# E-17_MIPI_DSI_MIPI_CSI.net
KiCad netlist of a schematic drawn in Altium Designer
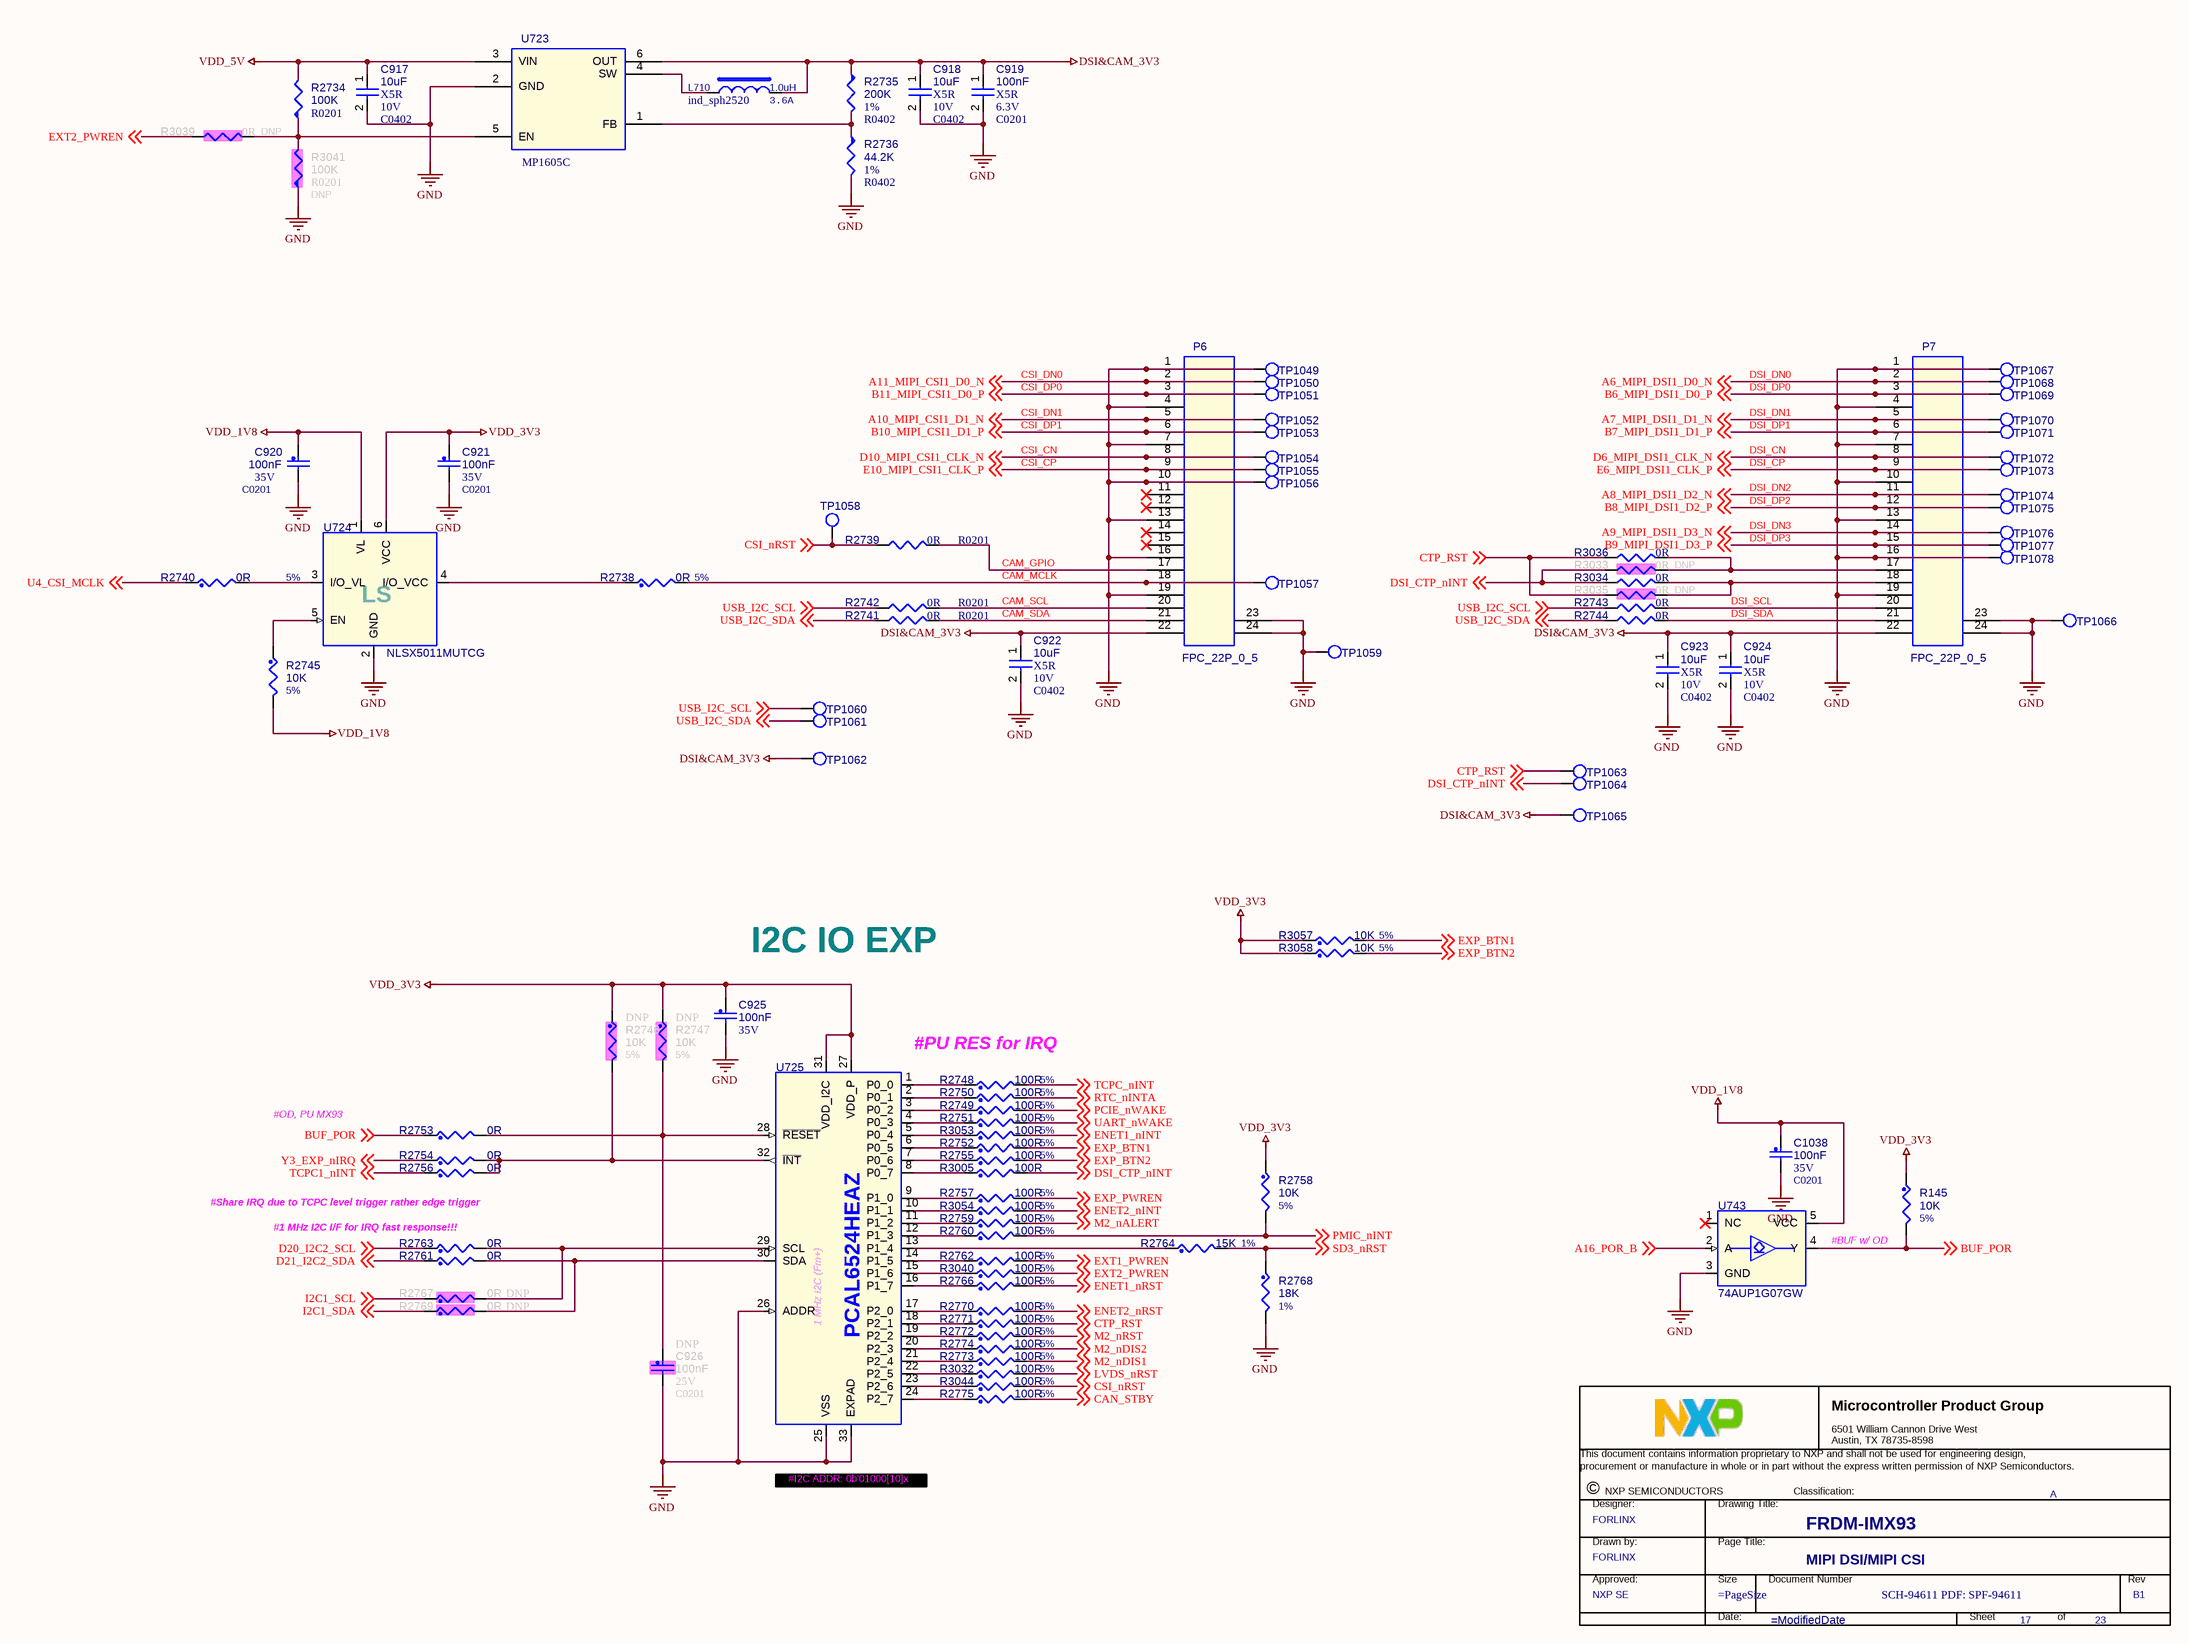
[diagram p0: E-17 MIPI DSI_MIPI CSI.SchDoc]

(export (version "E")
  (design (tool "Eeschema 10.0.6"))
  (components
    (comp (ref "C917")
      (value "10uF")
      (footprint "C0402")
      (description "0402,10uF,6.3V,+/-20%,X5R")
      (fields
        (field (name "VOLTAGE") "10V")
        (field (name "PCB FOOTPRINT") "C0402")
        (field (name "DIELECTRIC") "X5R")
        (field (name "TOLERANCE") "±20%")
        (field (name "MANUFACTURER") "murata")
        (field (name "CREATED BY") "JJJ")
      )
      (libsource (lib "*") (part "CAP NP"))
    )
    (comp (ref "C918")
      (value "10uF")
      (footprint "C0402")
      (description "0402,10uF,6.3V,+/-20%,X5R")
      (fields
        (field (name "VOLTAGE") "10V")
        (field (name "PCB FOOTPRINT") "C0402")
        (field (name "DIELECTRIC") "X5R")
        (field (name "MANUFACTURER") "TDK")
        (field (name "TOLERANCE") "10%")
        (field (name "CREATED BY") "JJJ")
      )
      (libsource (lib "*") (part "CAP NP"))
    )
    (comp (ref "C919")
      (value "100nF")
      (footprint "C0201")
      (description "0201,100nF,25V,+/-10%,X5R")
      (fields
        (field (name "VOLTAGE") "6.3V")
        (field (name "PCB FOOTPRINT") "C0201")
        (field (name "DIELECTRIC") "X5R")
        (field (name "MANUFACTURER") "FH(风华)")
        (field (name "TOLERANCE") "±10%")
        (field (name "CREATED BY") "JJJ")
      )
      (libsource (lib "*") (part "CAP NP"))
    )
    (comp (ref "C920")
      (value "100nF")
      (footprint "C0201")
      (description "0201,100nF,25V,+/-10%,X5R")
      (fields
        (field (name "PCB FOOTPRINT") "C0201")
        (field (name "VOLTAGE") "35V")
        (field (name "TOLERANCE") "10%")
      )
      (libsource (lib "*") (part "CAP_NP"))
    )
    (comp (ref "C921")
      (value "100nF")
      (footprint "C0201")
      (description "0201,100nF,25V,+/-10%,X5R")
      (fields
        (field (name "PCB FOOTPRINT") "C0201")
        (field (name "TOLERANCE") "10%")
        (field (name "VOLTAGE") "35V")
      )
      (libsource (lib "*") (part "CAP_NP"))
    )
    (comp (ref "C922")
      (value "10uF")
      (footprint "C0402")
      (description "0402,10uF,6.3V,+/-20%,X5R")
      (fields
        (field (name "VOLTAGE") "10V")
        (field (name "PCB FOOTPRINT") "C0402")
        (field (name "DIELECTRIC") "X5R")
        (field (name "MANUFACTURER") "TDK")
        (field (name "TOLERANCE") "10%")
        (field (name "CREATED BY") "JJJ")
      )
      (libsource (lib "*") (part "CAP NP"))
    )
    (comp (ref "C923")
      (value "10uF")
      (footprint "C0402")
      (description "0402,10uF,6.3V,+/-20%,X5R")
      (fields
        (field (name "VOLTAGE") "10V")
        (field (name "PCB FOOTPRINT") "C0402")
        (field (name "DIELECTRIC") "X5R")
        (field (name "MANUFACTURER") "TDK")
        (field (name "TOLERANCE") "10%")
        (field (name "CREATED BY") "JJJ")
      )
      (libsource (lib "*") (part "CAP NP"))
    )
    (comp (ref "C924")
      (value "10uF")
      (footprint "C0402")
      (description "0402,10uF,6.3V,+/-20%,X5R")
      (fields
        (field (name "VOLTAGE") "10V")
        (field (name "PCB FOOTPRINT") "C0402")
        (field (name "DIELECTRIC") "X5R")
        (field (name "TOLERANCE") "10%")
        (field (name "MANUFACTURER") "TDK")
        (field (name "CREATED BY") "JJJ")
      )
      (libsource (lib "*") (part "CAP NP"))
    )
    (comp (ref "C925")
      (value "100nF")
      (footprint "C0402")
      (description "0402,100nF,50V,+/-10%,X5R")
      (fields (field (name "TOLERANCE") "10%") (field (name "VOLTAGE") "35V"))
      (libsource (lib "*") (part "CAP_NP"))
    )
    (comp (ref "C926")
      (value "100nF")
      (footprint "C0201")
      (description "0201,100nF,25V,+/-10%,X5R")
      (fields
        (field (name "ASSY_OPT") "DNP")
        (field (name "PCB FOOTPRINT") "C0201")
        (field (name "TOLERANCE") "10%")
        (field (name "VOLTAGE") "25V")
      )
      (libsource (lib "*") (part "CAP_NP"))
    )
    (comp (ref "C1038")
      (value "100nF")
      (footprint "C0201")
      (description "0201,100nF,25V,+/-10%,X5R")
      (fields
        (field (name "PCB FOOTPRINT") "C0201")
        (field (name "TOLERANCE") "10%")
        (field (name "VOLTAGE") "35V")
      )
      (libsource (lib "*") (part "CAP_NP"))
    )
    (comp (ref "L710")
      (value "1.0uH")
      (footprint "ind_sph2520")
      (description "1uH ,2.5*2.0*1.2mm, 3.6A")
      (fields
        (field (name "ISAT") "3.6A")
        (field (name "PCB FOOTPRINT") "ind_sph2520")
        (field (name "MANUFACTURER") "TDK")
        (field (name "TOLERANCE") "20%")
        (field (name "CREATED BY") "JJJ")
      )
      (libsource (lib "*") (part "INDUCTORS OF FERRITE"))
    )
    (comp (ref "P6")
      (value "FPC_22P_0_5")
      (footprint "fpc_22p_0_5")
      (description "22P,0.5mm,A")
      (libsource (lib "*") (part "FPC_22P_0_5"))
    )
    (comp (ref "P7")
      (value "FPC_22P_0_5")
      (footprint "fpc_22p_0_5")
      (description "22P,0.5mm,A")
      (libsource (lib "*") (part "FPC_22P_0_5"))
    )
    (comp (ref "R145")
      (value "10K")
      (footprint "R0201")
      (description "0201,10K,+/-5%")
      (fields (field (name "TOLERANCE") "5%"))
      (libsource (lib "*") (part "RES"))
    )
    (comp (ref "R2734")
      (value "100K")
      (footprint "R0201")
      (description "0201,100K,+/-1%")
      (fields
        (field (name "TOLERANCE") "5%")
        (field (name "PCB FOOTPRINT") "R0201")
        (field (name "MANUFACTURER") "YAGEO")
        (field (name "CREATED BY") "YTL")
      )
      (libsource (lib "*") (part "RESISTOR5"))
    )
    (comp (ref "R2735")
      (value "200K")
      (footprint "R0402")
      (description "0402,200K,+/-1%")
      (fields
        (field (name "PCB FOOTPRINT") "R0402")
        (field (name "TOLERANCE") "1%")
        (field (name "MANUFACTURER") "YAGEO")
        (field (name "CREATED BY") "YTL")
      )
      (libsource (lib "*") (part "RESISTOR1"))
    )
    (comp (ref "R2736")
      (value "44.2K")
      (footprint "R0402")
      (description "0402,44.2K,+/-1%")
      (fields
        (field (name "PCB FOOTPRINT") "R0402")
        (field (name "TOLERANCE") "1%")
        (field (name "MANUFACTURER") "YAGEO")
        (field (name "CREATED BY") "YTL")
      )
      (libsource (lib "*") (part "RESISTOR1"))
    )
    (comp (ref "R2738")
      (value "0R")
      (footprint "R0201")
      (description "0201,0Ohm,+/-5%")
      (fields (field (name "VOLTAGE") "1/16W") (field (name "TOLERANCE") "5%"))
      (libsource (lib "*") (part "RES"))
    )
    (comp (ref "R2739")
      (value "0R")
      (footprint "R0201")
      (description "0201,0Ohm,+/-5%")
      (fields (field (name "PCB FOOTPRINT") "R0201"))
      (libsource (lib "*") (part "R0402,4.7K_Dup1"))
    )
    (comp (ref "R2740")
      (value "0R")
      (footprint "R0201")
      (description "0201,0Ohm,+/-5%")
      (fields (field (name "VOLTAGE") "1/16W") (field (name "TOLERANCE") "5%"))
      (libsource (lib "*") (part "RES"))
    )
    (comp (ref "R2741")
      (value "0R")
      (footprint "R0201")
      (description "0201,0Ohm,+/-5%")
      (fields (field (name "PCB FOOTPRINT") "R0201"))
      (libsource (lib "*") (part "R0402,4.7K_Dup1"))
    )
    (comp (ref "R2742")
      (value "0R")
      (footprint "R0201")
      (description "0201,0Ohm,+/-5%")
      (fields (field (name "PCB FOOTPRINT") "R0201"))
      (libsource (lib "*") (part "R0402,4.7K_Dup1"))
    )
    (comp (ref "R2743")
      (value "0R")
      (footprint "R0201")
      (description "0201,0Ohm,+/-5%")
      (libsource (lib "*") (part "R0402,4.7K_Dup1"))
    )
    (comp (ref "R2744")
      (value "0R")
      (footprint "R0201")
      (description "0201,0Ohm,+/-5%")
      (libsource (lib "*") (part "R0402,4.7K_Dup1"))
    )
    (comp (ref "R2745")
      (value "10K")
      (footprint "R0201")
      (description "0201,10K,+/-5%")
      (fields (field (name "TOLERANCE") "5%"))
      (libsource (lib "*") (part "RES"))
    )
    (comp (ref "R2746")
      (value "10K")
      (footprint "R0201")
      (description "0201,10K,+/-5%")
      (fields (field (name "ASSY_OPT") "DNP") (field (name "TOLERANCE") "5%"))
      (libsource (lib "*") (part "RES"))
    )
    (comp (ref "R2747")
      (value "10K")
      (footprint "R0201")
      (description "0201,10K,+/-5%")
      (fields (field (name "ASSY_OPT") "DNP") (field (name "TOLERANCE") "5%"))
      (libsource (lib "*") (part "RES"))
    )
    (comp (ref "R2748")
      (value "100R")
      (footprint "R0201")
      (description "0201,100Ohm,+/-1%")
      (fields (field (name "TOLERANCE") "5%"))
      (libsource (lib "*") (part "RES"))
    )
    (comp (ref "R2749")
      (value "100R")
      (footprint "R0201")
      (description "0201,100Ohm,+/-1%")
      (fields (field (name "TOLERANCE") "5%"))
      (libsource (lib "*") (part "RES"))
    )
    (comp (ref "R2750")
      (value "100R")
      (footprint "R0201")
      (description "0201,100Ohm,+/-1%")
      (fields (field (name "TOLERANCE") "5%"))
      (libsource (lib "*") (part "RES"))
    )
    (comp (ref "R2751")
      (value "100R")
      (footprint "R0201")
      (description "0201,100Ohm,+/-1%")
      (fields (field (name "TOLERANCE") "5%"))
      (libsource (lib "*") (part "RES"))
    )
    (comp (ref "R2752")
      (value "100R")
      (footprint "R0201")
      (description "0201,100Ohm,+/-1%")
      (fields (field (name "TOLERANCE") "5%"))
      (libsource (lib "*") (part "RES"))
    )
    (comp (ref "R2753")
      (value "0R")
      (footprint "R0201")
      (description "0201,0Ohm,+/-5%")
      (fields (field (name "VOLTAGE") "1/16W") (field (name "TOLERANCE") "5%"))
      (libsource (lib "*") (part "RES"))
    )
    (comp (ref "R2754")
      (value "0R")
      (footprint "R0201")
      (description "0201,0Ohm,+/-5%")
      (fields (field (name "TOLERANCE") "5%") (field (name "VOLTAGE") "1/16W"))
      (libsource (lib "*") (part "RES"))
    )
    (comp (ref "R2755")
      (value "100R")
      (footprint "R0201")
      (description "0201,100Ohm,+/-1%")
      (fields (field (name "TOLERANCE") "5%"))
      (libsource (lib "*") (part "RES"))
    )
    (comp (ref "R2756")
      (value "0R")
      (footprint "R0201")
      (description "0201,0Ohm,+/-5%")
      (fields (field (name "VOLTAGE") "1/16W") (field (name "TOLERANCE") "5%"))
      (libsource (lib "*") (part "RES"))
    )
    (comp (ref "R2757")
      (value "100R")
      (footprint "R0201")
      (description "0201,100Ohm,+/-1%")
      (fields (field (name "TOLERANCE") "5%"))
      (libsource (lib "*") (part "RES"))
    )
    (comp (ref "R2758")
      (value "10K")
      (footprint "R0201")
      (description "0201,10K,+/-5%")
      (fields (field (name "TOLERANCE") "5%"))
      (libsource (lib "*") (part "RES"))
    )
    (comp (ref "R2759")
      (value "100R")
      (footprint "R0201")
      (description "0201,100Ohm,+/-1%")
      (fields (field (name "TOLERANCE") "5%"))
      (libsource (lib "*") (part "RES"))
    )
    (comp (ref "R2760")
      (value "100R")
      (footprint "R0201")
      (description "0201,100Ohm,+/-1%")
      (fields (field (name "TOLERANCE") "5%"))
      (libsource (lib "*") (part "RES"))
    )
    (comp (ref "R2761")
      (value "0R")
      (footprint "R0201")
      (description "0201,0Ohm,+/-5%")
      (fields (field (name "TOLERANCE") "5%") (field (name "VOLTAGE") "1/16W"))
      (libsource (lib "*") (part "RES"))
    )
    (comp (ref "R2762")
      (value "100R")
      (footprint "R0201")
      (description "0201,100Ohm,+/-1%")
      (fields (field (name "TOLERANCE") "5%"))
      (libsource (lib "*") (part "RES"))
    )
    (comp (ref "R2763")
      (value "0R")
      (footprint "R0201")
      (description "0201,0Ohm,+/-5%")
      (fields (field (name "TOLERANCE") "5%") (field (name "VOLTAGE") "1/16W"))
      (libsource (lib "*") (part "RES"))
    )
    (comp (ref "R2764")
      (value "15K")
      (footprint "R0402")
      (description "0402,15K,+/-1%")
      (fields (field (name "TOLERANCE") "1%"))
      (libsource (lib "*") (part "RES"))
    )
    (comp (ref "R2766")
      (value "100R")
      (footprint "R0201")
      (description "0201,100Ohm,+/-1%")
      (fields (field (name "TOLERANCE") "5%"))
      (libsource (lib "*") (part "RES"))
    )
    (comp (ref "R2767")
      (value "0R")
      (footprint "R0201")
      (description "0201,0Ohm,+/-5%")
      (fields
        (field (name "ASSY_OPT") "DNP")
        (field (name "TOLERANCE") "5%")
        (field (name "VOLTAGE") "1/16W")
      )
      (libsource (lib "*") (part "RES"))
    )
    (comp (ref "R2768")
      (value "18K")
      (footprint "R0402")
      (description "0402,18K,+/-1%")
      (fields (field (name "VOLTAGE") "50V") (field (name "TOLERANCE") "1%"))
      (libsource (lib "*") (part "RES"))
    )
    (comp (ref "R2769")
      (value "0R")
      (footprint "R0201")
      (description "0201,0Ohm,+/-5%")
      (fields
        (field (name "ASSY_OPT") "DNP")
        (field (name "VOLTAGE") "1/16W")
        (field (name "TOLERANCE") "5%")
      )
      (libsource (lib "*") (part "RES"))
    )
    (comp (ref "R2770")
      (value "100R")
      (footprint "R0201")
      (description "0201,100Ohm,+/-1%")
      (fields (field (name "TOLERANCE") "5%"))
      (libsource (lib "*") (part "RES"))
    )
    (comp (ref "R2771")
      (value "100R")
      (footprint "R0201")
      (description "0201,100Ohm,+/-1%")
      (fields (field (name "TOLERANCE") "5%"))
      (libsource (lib "*") (part "RES"))
    )
    (comp (ref "R2772")
      (value "100R")
      (footprint "R0201")
      (description "0201,100Ohm,+/-1%")
      (fields (field (name "TOLERANCE") "5%"))
      (libsource (lib "*") (part "RES"))
    )
    (comp (ref "R2773")
      (value "100R")
      (footprint "R0201")
      (description "0201,100Ohm,+/-1%")
      (fields (field (name "TOLERANCE") "5%"))
      (libsource (lib "*") (part "RES"))
    )
    (comp (ref "R2774")
      (value "100R")
      (footprint "R0201")
      (description "0201,100Ohm,+/-1%")
      (fields (field (name "TOLERANCE") "5%"))
      (libsource (lib "*") (part "RES"))
    )
    (comp (ref "R2775")
      (value "100R")
      (footprint "R0201")
      (description "0201,100Ohm,+/-1%")
      (fields (field (name "TOLERANCE") "5%"))
      (libsource (lib "*") (part "RES"))
    )
    (comp (ref "R3005")
      (value "100R")
      (footprint "R0201")
      (description "0201,100Ohm,+/-1%")
      (fields (field (name "TOLERANCE") "5%"))
      (libsource (lib "*") (part "RES"))
    )
    (comp (ref "R3032")
      (value "100R")
      (footprint "R0201")
      (description "0201,100Ohm,+/-1%")
      (fields (field (name "TOLERANCE") "5%"))
      (libsource (lib "*") (part "RES"))
    )
    (comp (ref "R3033")
      (value "0R")
      (footprint "R0201")
      (description "0201,0Ohm,+/-5%")
      (fields (field (name "ASSY_OPT") "DNP"))
      (libsource (lib "*") (part "R0402,4.7K_Dup1"))
    )
    (comp (ref "R3034")
      (value "0R")
      (footprint "R0201")
      (description "0201,0Ohm,+/-5%")
      (libsource (lib "*") (part "R0402,4.7K_Dup1"))
    )
    (comp (ref "R3035")
      (value "0R")
      (footprint "R0201")
      (description "0201,0Ohm,+/-5%")
      (fields (field (name "ASSY_OPT") "DNP"))
      (libsource (lib "*") (part "R0402,4.7K_Dup1"))
    )
    (comp (ref "R3036")
      (value "0R")
      (footprint "R0201")
      (description "0201,0Ohm,+/-5%")
      (libsource (lib "*") (part "R0402,4.7K_Dup1"))
    )
    (comp (ref "R3039")
      (value "0R")
      (footprint "R0201")
      (description "0201,0Ohm,+/-5%")
      (fields (field (name "ASSY_OPT") "DNP"))
      (libsource (lib "*") (part "R0402,4.7K_Dup1"))
    )
    (comp (ref "R3040")
      (value "100R")
      (footprint "R0201")
      (description "0201,100Ohm,+/-1%")
      (fields (field (name "TOLERANCE") "5%"))
      (libsource (lib "*") (part "RES"))
    )
    (comp (ref "R3041")
      (value "100K")
      (footprint "R0201")
      (description "0201,100K,+/-1%")
      (fields
        (field (name "TOLERANCE") "5%")
        (field (name "PCB FOOTPRINT") "R0201")
        (field (name "MANUFACTURER") "YAGEO")
        (field (name "ASSY_OPT") "DNP")
        (field (name "CREATED BY") "YTL")
      )
      (libsource (lib "*") (part "RESISTOR5"))
    )
    (comp (ref "R3044")
      (value "100R")
      (footprint "R0201")
      (description "0201,100Ohm,+/-1%")
      (fields (field (name "TOLERANCE") "5%"))
      (libsource (lib "*") (part "RES"))
    )
    (comp (ref "R3053")
      (value "100R")
      (footprint "R0201")
      (description "0201,100Ohm,+/-1%")
      (fields (field (name "TOLERANCE") "5%"))
      (libsource (lib "*") (part "RES"))
    )
    (comp (ref "R3054")
      (value "100R")
      (footprint "R0201")
      (description "0201,100Ohm,+/-1%")
      (fields (field (name "TOLERANCE") "5%"))
      (libsource (lib "*") (part "RES"))
    )
    (comp (ref "R3057")
      (value "10K")
      (footprint "R0201")
      (description "0201,10K,+/-5%")
      (fields (field (name "TOLERANCE") "5%"))
      (libsource (lib "*") (part "RES"))
    )
    (comp (ref "R3058")
      (value "10K")
      (footprint "R0201")
      (description "0201,10K,+/-5%")
      (fields (field (name "TOLERANCE") "5%"))
      (libsource (lib "*") (part "RES"))
    )
    (comp (ref "TP1049")
      (value "TPAD_020")
      (footprint "tpad_020")
      (description "no part to order")
      (libsource (lib "*") (part "T POINT R"))
    )
    (comp (ref "TP1050")
      (value "TPAD_020")
      (footprint "tpad_020")
      (description "no part to order")
      (libsource (lib "*") (part "T POINT R"))
    )
    (comp (ref "TP1051")
      (value "TPAD_020")
      (footprint "tpad_020")
      (description "no part to order")
      (libsource (lib "*") (part "T POINT R"))
    )
    (comp (ref "TP1052")
      (value "TPAD_020")
      (footprint "tpad_020")
      (description "no part to order")
      (libsource (lib "*") (part "T POINT R"))
    )
    (comp (ref "TP1053")
      (value "TPAD_020")
      (footprint "tpad_020")
      (description "no part to order")
      (libsource (lib "*") (part "T POINT R"))
    )
    (comp (ref "TP1054")
      (value "TPAD_020")
      (footprint "tpad_020")
      (description "no part to order")
      (libsource (lib "*") (part "T POINT R"))
    )
    (comp (ref "TP1055")
      (value "TPAD_020")
      (footprint "tpad_020")
      (description "no part to order")
      (libsource (lib "*") (part "T POINT R"))
    )
    (comp (ref "TP1056")
      (value "TPAD_020")
      (footprint "tpad_020")
      (description "no part to order")
      (libsource (lib "*") (part "T POINT R"))
    )
    (comp (ref "TP1057")
      (value "TPAD_020")
      (footprint "tpad_020")
      (description "no part to order")
      (libsource (lib "*") (part "T POINT R"))
    )
    (comp (ref "TP1058")
      (value "TPAD_020")
      (footprint "tpad_020")
      (description "no part to order")
      (libsource (lib "*") (part "T POINT R"))
    )
    (comp (ref "TP1059")
      (value "TPAD_020")
      (footprint "tpad_020")
      (description "no part to order")
      (libsource (lib "*") (part "T POINT R"))
    )
    (comp (ref "TP1060")
      (value "TPAD_020")
      (footprint "tpad_020")
      (description "no part to order")
      (libsource (lib "*") (part "T POINT R"))
    )
    (comp (ref "TP1061")
      (value "TPAD_020")
      (footprint "tpad_020")
      (description "no part to order")
      (libsource (lib "*") (part "T POINT R"))
    )
    (comp (ref "TP1062")
      (value "TPAD_020")
      (footprint "tpad_020")
      (description "no part to order")
      (libsource (lib "*") (part "T POINT R"))
    )
    (comp (ref "TP1063")
      (value "TPAD_020")
      (footprint "tpad_020")
      (description "no part to order")
      (libsource (lib "*") (part "T POINT R"))
    )
    (comp (ref "TP1064")
      (value "TPAD_020")
      (footprint "tpad_020")
      (description "no part to order")
      (libsource (lib "*") (part "T POINT R"))
    )
    (comp (ref "TP1065")
      (value "TPAD_020")
      (footprint "tpad_020")
      (description "no part to order")
      (libsource (lib "*") (part "T POINT R"))
    )
    (comp (ref "TP1066")
      (value "TPAD_020")
      (footprint "tpad_020")
      (description "no part to order")
      (libsource (lib "*") (part "T POINT R"))
    )
    (comp (ref "TP1067")
      (value "TPAD_020")
      (footprint "tpad_020")
      (description "no part to order")
      (libsource (lib "*") (part "T POINT R"))
    )
    (comp (ref "TP1068")
      (value "TPAD_020")
      (footprint "tpad_020")
      (description "no part to order")
      (libsource (lib "*") (part "T POINT R"))
    )
    (comp (ref "TP1069")
      (value "TPAD_020")
      (footprint "tpad_020")
      (description "no part to order")
      (libsource (lib "*") (part "T POINT R"))
    )
    (comp (ref "TP1070")
      (value "TPAD_020")
      (footprint "tpad_020")
      (description "no part to order")
      (libsource (lib "*") (part "T POINT R"))
    )
    (comp (ref "TP1071")
      (value "TPAD_020")
      (footprint "tpad_020")
      (description "no part to order")
      (libsource (lib "*") (part "T POINT R"))
    )
    (comp (ref "TP1072")
      (value "TPAD_020")
      (footprint "tpad_020")
      (description "no part to order")
      (libsource (lib "*") (part "T POINT R"))
    )
    (comp (ref "TP1073")
      (value "TPAD_020")
      (footprint "tpad_020")
      (description "no part to order")
      (libsource (lib "*") (part "T POINT R"))
    )
    (comp (ref "TP1074")
      (value "TPAD_020")
      (footprint "tpad_020")
      (description "no part to order")
      (libsource (lib "*") (part "T POINT R"))
    )
    (comp (ref "TP1075")
      (value "TPAD_020")
      (footprint "tpad_020")
      (description "no part to order")
      (libsource (lib "*") (part "T POINT R"))
    )
    (comp (ref "TP1076")
      (value "TPAD_020")
      (footprint "tpad_020")
      (description "no part to order")
      (libsource (lib "*") (part "T POINT R"))
    )
    (comp (ref "TP1077")
      (value "TPAD_020")
      (footprint "tpad_020")
      (description "no part to order")
      (libsource (lib "*") (part "T POINT R"))
    )
    (comp (ref "TP1078")
      (value "TPAD_020")
      (footprint "tpad_020")
      (description "no part to order")
      (libsource (lib "*") (part "T POINT R"))
    )
    (comp (ref "U723")
      (value "MP1605C")
      (footprint "SOT563")
      (description "MP1605GTF,SOT563")
      (libsource (lib "*") (part "MP1605C"))
    )
    (comp (ref "U724")
      (value "NLSX5011MUTCG")
      (footprint "udfn6_0p4_1p2x1")
      (description "NLSX5011MUTCG,UDFN6,1.2*1.0,0.4P,One 100Mb/s configurable dual power level converter")
      (fields (field (name "VOLTAGE") "0.9-4.5V"))
      (libsource (lib "*") (part "NLSX5011_0"))
    )
    (comp (ref "U725")
      (value "PCAL6524HEAZ")
      (footprint "uqfn32_0p5_5x5_ep3x3")
      (description "PCAL6524HEAZ,QFN32")
      (fields (field (name "VOLTAGE") "0.8-3.6V/1.65-5.5"))
      (libsource (lib "*") (part "PCAL6524HE_QFN"))
    )
    (comp (ref "U743")
      (value "74AUP1G07GW")
      (footprint "sc70-5")
      (description "74AUP1G07GW,TSSOP5,1.2*2mm,Low-power buffer with open-drain output")
      (fields (field (name "VOLTAGE") "0.8-3.6V"))
      (libsource (lib "*") (part "74AUP1G07GW"))
    )
  )
  (nets
    (net (code "1") (name "/CAM_GPIO") (class "Default")
      (node (ref "P6") (pin "17") (pinfunction "17_17") (pintype "passive"))
      (node (ref "R2739") (pin "2") (pinfunction "2_2") (pintype "passive"))
    )
    (net (code "2") (name "/CAM_MCLK") (class "Default")
      (node (ref "P6") (pin "18") (pinfunction "18_18") (pintype "passive"))
      (node (ref "R2738") (pin "2") (pinfunction "2_2") (pintype "passive"))
      (node (ref "TP1057") (pin "1") (pinfunction "TP_1") (pintype "passive"))
    )
    (net (code "3") (name "/CAM_SCL") (class "Default")
      (node (ref "P6") (pin "20") (pinfunction "20_20") (pintype "passive"))
      (node (ref "R2742") (pin "2") (pinfunction "2_2") (pintype "passive"))
    )
    (net (code "4") (name "/CAM_SDA") (class "Default")
      (node (ref "P6") (pin "21") (pinfunction "21_21") (pintype "passive"))
      (node (ref "R2741") (pin "2") (pinfunction "2_2") (pintype "passive"))
    )
    (net (code "5") (name "/DSI_SCL") (class "Default")
      (node (ref "P7") (pin "20") (pinfunction "20_20") (pintype "passive"))
      (node (ref "R2743") (pin "2") (pinfunction "2_2") (pintype "passive"))
    )
    (net (code "6") (name "/DSI_SDA") (class "Default")
      (node (ref "P7") (pin "21") (pinfunction "21_21") (pintype "passive"))
      (node (ref "R2744") (pin "2") (pinfunction "2_2") (pintype "passive"))
    )
    (net (code "7") (name "A6_MIPI_DSI1_D0_N") (class "Default")
      (node (ref "P7") (pin "2") (pinfunction "2_2") (pintype "passive"))
      (node (ref "TP1068") (pin "1") (pinfunction "TP_1") (pintype "passive"))
    )
    (net (code "8") (name "A7_MIPI_DSI1_D1_N") (class "Default")
      (node (ref "P7") (pin "5") (pinfunction "5_5") (pintype "passive"))
      (node (ref "TP1070") (pin "1") (pinfunction "TP_1") (pintype "passive"))
    )
    (net (code "9") (name "A8_MIPI_DSI1_D2_N") (class "Default")
      (node (ref "P7") (pin "11") (pinfunction "11_11") (pintype "passive"))
      (node (ref "TP1074") (pin "1") (pinfunction "TP_1") (pintype "passive"))
    )
    (net (code "10") (name "A9_MIPI_DSI1_D3_N") (class "Default")
      (node (ref "P7") (pin "14") (pinfunction "14_14") (pintype "passive"))
      (node (ref "TP1076") (pin "1") (pinfunction "TP_1") (pintype "passive"))
    )
    (net (code "11") (name "A10_MIPI_CSI1_D1_N") (class "Default")
      (node (ref "P6") (pin "5") (pinfunction "5_5") (pintype "passive"))
      (node (ref "TP1052") (pin "1") (pinfunction "TP_1") (pintype "passive"))
    )
    (net (code "12") (name "A11_MIPI_CSI1_D0_N") (class "Default")
      (node (ref "P6") (pin "2") (pinfunction "2_2") (pintype "passive"))
      (node (ref "TP1050") (pin "1") (pinfunction "TP_1") (pintype "passive"))
    )
    (net (code "13") (name "A16_POR_B") (class "Default")
      (node (ref "U743") (pin "2") (pinfunction "A_2") (pintype "input"))
    )
    (net (code "14") (name "B6_MIPI_DSI1_D0_P") (class "Default")
      (node (ref "P7") (pin "3") (pinfunction "3_3") (pintype "passive"))
      (node (ref "TP1069") (pin "1") (pinfunction "TP_1") (pintype "passive"))
    )
    (net (code "15") (name "B7_MIPI_DSI1_D1_P") (class "Default")
      (node (ref "P7") (pin "6") (pinfunction "6_6") (pintype "passive"))
      (node (ref "TP1071") (pin "1") (pinfunction "TP_1") (pintype "passive"))
    )
    (net (code "16") (name "B8_MIPI_DSI1_D2_P") (class "Default")
      (node (ref "P7") (pin "12") (pinfunction "12_12") (pintype "passive"))
      (node (ref "TP1075") (pin "1") (pinfunction "TP_1") (pintype "passive"))
    )
    (net (code "17") (name "B9_MIPI_DSI1_D3_P") (class "Default")
      (node (ref "P7") (pin "15") (pinfunction "15_15") (pintype "passive"))
      (node (ref "TP1077") (pin "1") (pinfunction "TP_1") (pintype "passive"))
    )
    (net (code "18") (name "B10_MIPI_CSI1_D1_P") (class "Default")
      (node (ref "P6") (pin "6") (pinfunction "6_6") (pintype "passive"))
      (node (ref "TP1053") (pin "1") (pinfunction "TP_1") (pintype "passive"))
    )
    (net (code "19") (name "B11_MIPI_CSI1_D0_P") (class "Default")
      (node (ref "P6") (pin "3") (pinfunction "3_3") (pintype "passive"))
      (node (ref "TP1051") (pin "1") (pinfunction "TP_1") (pintype "passive"))
    )
    (net (code "20") (name "BUF_POR") (class "Default")
      (node (ref "R145") (pin "2") (pinfunction "2_2") (pintype "passive"))
      (node (ref "R2753") (pin "1") (pinfunction "1_1") (pintype "passive"))
      (node (ref "U743") (pin "4") (pinfunction "Y_4") (pintype "open_collector"))
    )
    (net (code "21") (name "CAN_STBY") (class "Default")
      (node (ref "R2775") (pin "2") (pinfunction "2_2") (pintype "passive"))
    )
    (net (code "22") (name "CSI_nRST") (class "Default")
      (node (ref "R2739") (pin "1") (pinfunction "1_1") (pintype "passive"))
      (node (ref "R3044") (pin "2") (pinfunction "2_2") (pintype "passive"))
      (node (ref "TP1058") (pin "1") (pinfunction "TP_1") (pintype "passive"))
    )
    (net (code "23") (name "CTP_RST") (class "Default")
      (node (ref "R2771") (pin "2") (pinfunction "2_2") (pintype "passive"))
      (node (ref "R3035") (pin "1") (pinfunction "1_1") (pintype "passive"))
      (node (ref "R3036") (pin "1") (pinfunction "1_1") (pintype "passive"))
      (node (ref "TP1063") (pin "1") (pinfunction "TP_1") (pintype "passive"))
    )
    (net (code "24") (name "D6_MIPI_DSI1_CLK_N") (class "Default")
      (node (ref "P7") (pin "8") (pinfunction "8_8") (pintype "passive"))
      (node (ref "TP1072") (pin "1") (pinfunction "TP_1") (pintype "passive"))
    )
    (net (code "25") (name "D10_MIPI_CSI1_CLK_N") (class "Default")
      (node (ref "P6") (pin "8") (pinfunction "8_8") (pintype "passive"))
      (node (ref "TP1054") (pin "1") (pinfunction "TP_1") (pintype "passive"))
    )
    (net (code "26") (name "D20_I2C2_SCL") (class "Default")
      (node (ref "R2763") (pin "1") (pinfunction "1_1") (pintype "passive"))
    )
    (net (code "27") (name "D21_I2C2_SDA") (class "Default")
      (node (ref "R2761") (pin "1") (pinfunction "1_1") (pintype "passive"))
    )
    (net (code "28") (name "DSI&CAM_3V3") (class "Default")
      (node (ref "C918") (pin "1") (pinfunction "1_1") (pintype "passive"))
      (node (ref "C919") (pin "1") (pinfunction "1_1") (pintype "passive"))
      (node (ref "C922") (pin "1") (pinfunction "1_1") (pintype "passive"))
      (node (ref "C923") (pin "1") (pinfunction "1_1") (pintype "passive"))
      (node (ref "C924") (pin "1") (pinfunction "1_1") (pintype "passive"))
      (node (ref "L710") (pin "2") (pinfunction "2_2") (pintype "passive"))
      (node (ref "P6") (pin "22") (pinfunction "22_22") (pintype "passive"))
      (node (ref "P7") (pin "22") (pinfunction "22_22") (pintype "passive"))
      (node (ref "R2735") (pin "1") (pinfunction "1_1") (pintype "passive"))
      (node (ref "TP1062") (pin "1") (pinfunction "TP_1") (pintype "passive"))
      (node (ref "TP1065") (pin "1") (pinfunction "TP_1") (pintype "passive"))
      (node (ref "U723") (pin "6") (pinfunction "OUT_6") (pintype "passive"))
    )
    (net (code "29") (name "DSI_CTP_nINT") (class "Default")
      (node (ref "R3005") (pin "2") (pinfunction "2_2") (pintype "passive"))
      (node (ref "R3033") (pin "1") (pinfunction "1_1") (pintype "passive"))
      (node (ref "R3034") (pin "1") (pinfunction "1_1") (pintype "passive"))
      (node (ref "TP1064") (pin "1") (pinfunction "TP_1") (pintype "passive"))
    )
    (net (code "30") (name "E6_MIPI_DSI1_CLK_P") (class "Default")
      (node (ref "P7") (pin "9") (pinfunction "9_9") (pintype "passive"))
      (node (ref "TP1073") (pin "1") (pinfunction "TP_1") (pintype "passive"))
    )
    (net (code "31") (name "E10_MIPI_CSI1_CLK_P") (class "Default")
      (node (ref "P6") (pin "9") (pinfunction "9_9") (pintype "passive"))
      (node (ref "TP1055") (pin "1") (pinfunction "TP_1") (pintype "passive"))
    )
    (net (code "32") (name "ENET1_nINT") (class "Default")
      (node (ref "R3053") (pin "2") (pinfunction "2_2") (pintype "passive"))
    )
    (net (code "33") (name "ENET1_nRST") (class "Default")
      (node (ref "R2766") (pin "2") (pinfunction "2_2") (pintype "passive"))
    )
    (net (code "34") (name "ENET2_nINT") (class "Default")
      (node (ref "R3054") (pin "2") (pinfunction "2_2") (pintype "passive"))
    )
    (net (code "35") (name "ENET2_nRST") (class "Default")
      (node (ref "R2770") (pin "2") (pinfunction "2_2") (pintype "passive"))
    )
    (net (code "36") (name "EXP_BTN1") (class "Default")
      (node (ref "R2752") (pin "2") (pinfunction "2_2") (pintype "passive"))
      (node (ref "R3057") (pin "2") (pinfunction "2_2") (pintype "passive"))
    )
    (net (code "37") (name "EXP_BTN2") (class "Default")
      (node (ref "R2755") (pin "2") (pinfunction "2_2") (pintype "passive"))
      (node (ref "R3058") (pin "2") (pinfunction "2_2") (pintype "passive"))
    )
    (net (code "38") (name "EXP_PWREN") (class "Default")
      (node (ref "R2757") (pin "2") (pinfunction "2_2") (pintype "passive"))
    )
    (net (code "39") (name "EXT1_PWREN") (class "Default")
      (node (ref "R2762") (pin "2") (pinfunction "2_2") (pintype "passive"))
    )
    (net (code "40") (name "EXT2_PWREN") (class "Default")
      (node (ref "R3039") (pin "1") (pinfunction "1_1") (pintype "passive"))
      (node (ref "R3040") (pin "2") (pinfunction "2_2") (pintype "passive"))
    )
    (net (code "41") (name "GND") (class "Default")
      (node (ref "C1038") (pin "2") (pinfunction "2_2") (pintype "passive"))
      (node (ref "C917") (pin "2") (pinfunction "2_2") (pintype "passive"))
      (node (ref "C918") (pin "2") (pinfunction "2_2") (pintype "passive"))
      (node (ref "C919") (pin "2") (pinfunction "2_2") (pintype "passive"))
      (node (ref "C920") (pin "2") (pinfunction "2_2") (pintype "passive"))
      (node (ref "C921") (pin "2") (pinfunction "2_2") (pintype "passive"))
      (node (ref "C922") (pin "2") (pinfunction "2_2") (pintype "passive"))
      (node (ref "C923") (pin "2") (pinfunction "2_2") (pintype "passive"))
      (node (ref "C924") (pin "2") (pinfunction "2_2") (pintype "passive"))
      (node (ref "C925") (pin "2") (pinfunction "2_2") (pintype "passive"))
      (node (ref "C926") (pin "2") (pinfunction "2_2") (pintype "passive"))
      (node (ref "P6") (pin "1") (pinfunction "1_1") (pintype "passive"))
      (node (ref "P6") (pin "10") (pinfunction "10_10") (pintype "passive"))
      (node (ref "P6") (pin "13") (pinfunction "13_13") (pintype "passive"))
      (node (ref "P6") (pin "16") (pinfunction "16_16") (pintype "passive"))
      (node (ref "P6") (pin "19") (pinfunction "19_19") (pintype "passive"))
      (node (ref "P6") (pin "23") (pinfunction "23_23") (pintype "passive"))
      (node (ref "P6") (pin "24") (pinfunction "24_24") (pintype "passive"))
      (node (ref "P6") (pin "4") (pinfunction "4_4") (pintype "passive"))
      (node (ref "P6") (pin "7") (pinfunction "7_7") (pintype "passive"))
      (node (ref "P7") (pin "1") (pinfunction "1_1") (pintype "passive"))
      (node (ref "P7") (pin "10") (pinfunction "10_10") (pintype "passive"))
      (node (ref "P7") (pin "13") (pinfunction "13_13") (pintype "passive"))
      (node (ref "P7") (pin "16") (pinfunction "16_16") (pintype "passive"))
      (node (ref "P7") (pin "19") (pinfunction "19_19") (pintype "passive"))
      (node (ref "P7") (pin "23") (pinfunction "23_23") (pintype "passive"))
      (node (ref "P7") (pin "24") (pinfunction "24_24") (pintype "passive"))
      (node (ref "P7") (pin "4") (pinfunction "4_4") (pintype "passive"))
      (node (ref "P7") (pin "7") (pinfunction "7_7") (pintype "passive"))
      (node (ref "R2736") (pin "2") (pinfunction "2_2") (pintype "passive"))
      (node (ref "R2768") (pin "2") (pinfunction "2_2") (pintype "passive"))
      (node (ref "R3041") (pin "1") (pinfunction "1_1") (pintype "passive"))
      (node (ref "TP1049") (pin "1") (pinfunction "TP_1") (pintype "passive"))
      (node (ref "TP1056") (pin "1") (pinfunction "TP_1") (pintype "passive"))
      (node (ref "TP1059") (pin "1") (pinfunction "TP_1") (pintype "passive"))
      (node (ref "TP1066") (pin "1") (pinfunction "TP_1") (pintype "passive"))
      (node (ref "TP1067") (pin "1") (pinfunction "TP_1") (pintype "passive"))
      (node (ref "TP1078") (pin "1") (pinfunction "TP_1") (pintype "passive"))
      (node (ref "U723") (pin "2") (pinfunction "GND_2") (pintype "passive"))
      (node (ref "U724") (pin "2") (pinfunction "GND_2") (pintype "power_in"))
      (node (ref "U725") (pin "25") (pinfunction "VSS_25") (pintype "power_in"))
      (node (ref "U725") (pin "26") (pinfunction "ADDR_26") (pintype "input"))
      (node (ref "U725") (pin "33") (pinfunction "EXPAD_33") (pintype "passive"))
      (node (ref "U743") (pin "3") (pinfunction "GND_3") (pintype "power_in"))
    )
    (net (code "42") (name "I2C1_SCL") (class "Default")
      (node (ref "R2767") (pin "1") (pinfunction "1_1") (pintype "passive"))
    )
    (net (code "43") (name "I2C1_SDA") (class "Default")
      (node (ref "R2769") (pin "1") (pinfunction "1_1") (pintype "passive"))
    )
    (net (code "44") (name "LVDS_nRST") (class "Default")
      (node (ref "R3032") (pin "2") (pinfunction "2_2") (pintype "passive"))
    )
    (net (code "45") (name "M2_nALERT") (class "Default")
      (node (ref "R2759") (pin "2") (pinfunction "2_2") (pintype "passive"))
    )
    (net (code "46") (name "M2_nDIS1") (class "Default")
      (node (ref "R2773") (pin "2") (pinfunction "2_2") (pintype "passive"))
    )
    (net (code "47") (name "M2_nDIS2") (class "Default")
      (node (ref "R2774") (pin "2") (pinfunction "2_2") (pintype "passive"))
    )
    (net (code "48") (name "M2_nRST") (class "Default")
      (node (ref "R2772") (pin "2") (pinfunction "2_2") (pintype "passive"))
    )
    (net (code "49") (name "Net-(P7-Pad17)") (class "Default")
      (node (ref "P7") (pin "17") (pinfunction "17_17") (pintype "passive"))
      (node (ref "R3033") (pin "2") (pinfunction "2_2") (pintype "passive"))
      (node (ref "R3036") (pin "2") (pinfunction "2_2") (pintype "passive"))
    )
    (net (code "50") (name "Net-(P7-Pad18)") (class "Default")
      (node (ref "P7") (pin "18") (pinfunction "18_18") (pintype "passive"))
      (node (ref "R3034") (pin "2") (pinfunction "2_2") (pintype "passive"))
      (node (ref "R3035") (pin "2") (pinfunction "2_2") (pintype "passive"))
    )
    (net (code "51") (name "Net-(U723-EN)") (class "Default")
      (node (ref "R2734") (pin "1") (pinfunction "1_1") (pintype "passive"))
      (node (ref "R3039") (pin "2") (pinfunction "2_2") (pintype "passive"))
      (node (ref "R3041") (pin "2") (pinfunction "2_2") (pintype "passive"))
      (node (ref "U723") (pin "5") (pinfunction "EN_5") (pintype "passive"))
    )
    (net (code "52") (name "Net-(U723-FB)") (class "Default")
      (node (ref "R2735") (pin "2") (pinfunction "2_2") (pintype "passive"))
      (node (ref "R2736") (pin "1") (pinfunction "1_1") (pintype "passive"))
      (node (ref "U723") (pin "1") (pinfunction "FB_1") (pintype "passive"))
    )
    (net (code "53") (name "Net-(U723-SW)") (class "Default")
      (node (ref "L710") (pin "1") (pinfunction "1_1") (pintype "passive"))
      (node (ref "U723") (pin "4") (pinfunction "SW_4") (pintype "passive"))
    )
    (net (code "54") (name "Net-(U724-EN)") (class "Default")
      (node (ref "R2745") (pin "1") (pinfunction "1_1") (pintype "passive"))
      (node (ref "U724") (pin "5") (pinfunction "EN_5") (pintype "input"))
    )
    (net (code "55") (name "Net-(U724-I{slash}O_VCC)") (class "Default")
      (node (ref "R2738") (pin "1") (pinfunction "1_1") (pintype "passive"))
      (node (ref "U724") (pin "4") (pinfunction "I/O_VCC_4") (pintype "bidirectional"))
    )
    (net (code "56") (name "Net-(U724-I{slash}O_VL)") (class "Default")
      (node (ref "R2740") (pin "2") (pinfunction "2_2") (pintype "passive"))
      (node (ref "U724") (pin "3") (pinfunction "I/O_VL_3") (pintype "bidirectional"))
    )
    (net (code "57") (name "Net-(U725-P0_0)") (class "Default")
      (node (ref "R2748") (pin "1") (pinfunction "1_1") (pintype "passive"))
      (node (ref "U725") (pin "1") (pinfunction "P0_0_1") (pintype "bidirectional"))
    )
    (net (code "58") (name "Net-(U725-P0_1)") (class "Default")
      (node (ref "R2750") (pin "1") (pinfunction "1_1") (pintype "passive"))
      (node (ref "U725") (pin "2") (pinfunction "P0_1_2") (pintype "bidirectional"))
    )
    (net (code "59") (name "Net-(U725-P0_2)") (class "Default")
      (node (ref "R2749") (pin "1") (pinfunction "1_1") (pintype "passive"))
      (node (ref "U725") (pin "3") (pinfunction "P0_2_3") (pintype "bidirectional"))
    )
    (net (code "60") (name "Net-(U725-P0_3)") (class "Default")
      (node (ref "R2751") (pin "1") (pinfunction "1_1") (pintype "passive"))
      (node (ref "U725") (pin "4") (pinfunction "P0_3_4") (pintype "bidirectional"))
    )
    (net (code "61") (name "Net-(U725-P0_4)") (class "Default")
      (node (ref "R3053") (pin "1") (pinfunction "1_1") (pintype "passive"))
      (node (ref "U725") (pin "5") (pinfunction "P0_4_5") (pintype "bidirectional"))
    )
    (net (code "62") (name "Net-(U725-P0_5)") (class "Default")
      (node (ref "R2752") (pin "1") (pinfunction "1_1") (pintype "passive"))
      (node (ref "U725") (pin "6") (pinfunction "P0_5_6") (pintype "bidirectional"))
    )
    (net (code "63") (name "Net-(U725-P0_6)") (class "Default")
      (node (ref "R2755") (pin "1") (pinfunction "1_1") (pintype "passive"))
      (node (ref "U725") (pin "7") (pinfunction "P0_6_7") (pintype "bidirectional"))
    )
    (net (code "64") (name "Net-(U725-P0_7)") (class "Default")
      (node (ref "R3005") (pin "1") (pinfunction "1_1") (pintype "passive"))
      (node (ref "U725") (pin "8") (pinfunction "P0_7_8") (pintype "bidirectional"))
    )
    (net (code "65") (name "Net-(U725-P1_0)") (class "Default")
      (node (ref "R2757") (pin "1") (pinfunction "1_1") (pintype "passive"))
      (node (ref "U725") (pin "9") (pinfunction "P1_0_9") (pintype "bidirectional"))
    )
    (net (code "66") (name "Net-(U725-P1_1)") (class "Default")
      (node (ref "R3054") (pin "1") (pinfunction "1_1") (pintype "passive"))
      (node (ref "U725") (pin "10") (pinfunction "P1_1_10") (pintype "bidirectional"))
    )
    (net (code "67") (name "Net-(U725-P1_2)") (class "Default")
      (node (ref "R2759") (pin "1") (pinfunction "1_1") (pintype "passive"))
      (node (ref "U725") (pin "11") (pinfunction "P1_2_11") (pintype "bidirectional"))
    )
    (net (code "68") (name "Net-(U725-P1_3)") (class "Default")
      (node (ref "R2760") (pin "1") (pinfunction "1_1") (pintype "passive"))
      (node (ref "U725") (pin "12") (pinfunction "P1_3_12") (pintype "bidirectional"))
    )
    (net (code "69") (name "Net-(U725-P1_4)") (class "Default")
      (node (ref "R2764") (pin "1") (pinfunction "1_1") (pintype "passive"))
      (node (ref "U725") (pin "13") (pinfunction "P1_4_13") (pintype "bidirectional"))
    )
    (net (code "70") (name "Net-(U725-P1_5)") (class "Default")
      (node (ref "R2762") (pin "1") (pinfunction "1_1") (pintype "passive"))
      (node (ref "U725") (pin "14") (pinfunction "P1_5_14") (pintype "bidirectional"))
    )
    (net (code "71") (name "Net-(U725-P1_6)") (class "Default")
      (node (ref "R3040") (pin "1") (pinfunction "1_1") (pintype "passive"))
      (node (ref "U725") (pin "15") (pinfunction "P1_6_15") (pintype "bidirectional"))
    )
    (net (code "72") (name "Net-(U725-P1_7)") (class "Default")
      (node (ref "R2766") (pin "1") (pinfunction "1_1") (pintype "passive"))
      (node (ref "U725") (pin "16") (pinfunction "P1_7_16") (pintype "bidirectional"))
    )
    (net (code "73") (name "Net-(U725-P2_0)") (class "Default")
      (node (ref "R2770") (pin "1") (pinfunction "1_1") (pintype "passive"))
      (node (ref "U725") (pin "17") (pinfunction "P2_0_17") (pintype "bidirectional"))
    )
    (net (code "74") (name "Net-(U725-P2_1)") (class "Default")
      (node (ref "R2771") (pin "1") (pinfunction "1_1") (pintype "passive"))
      (node (ref "U725") (pin "18") (pinfunction "P2_1_18") (pintype "bidirectional"))
    )
    (net (code "75") (name "Net-(U725-P2_2)") (class "Default")
      (node (ref "R2772") (pin "1") (pinfunction "1_1") (pintype "passive"))
      (node (ref "U725") (pin "19") (pinfunction "P2_2_19") (pintype "bidirectional"))
    )
    (net (code "76") (name "Net-(U725-P2_3)") (class "Default")
      (node (ref "R2774") (pin "1") (pinfunction "1_1") (pintype "passive"))
      (node (ref "U725") (pin "20") (pinfunction "P2_3_20") (pintype "bidirectional"))
    )
    (net (code "77") (name "Net-(U725-P2_4)") (class "Default")
      (node (ref "R2773") (pin "1") (pinfunction "1_1") (pintype "passive"))
      (node (ref "U725") (pin "21") (pinfunction "P2_4_21") (pintype "bidirectional"))
    )
    (net (code "78") (name "Net-(U725-P2_5)") (class "Default")
      (node (ref "R3032") (pin "1") (pinfunction "1_1") (pintype "passive"))
      (node (ref "U725") (pin "22") (pinfunction "P2_5_22") (pintype "bidirectional"))
    )
    (net (code "79") (name "Net-(U725-P2_6)") (class "Default")
      (node (ref "R3044") (pin "1") (pinfunction "1_1") (pintype "passive"))
      (node (ref "U725") (pin "23") (pinfunction "P2_6_23") (pintype "bidirectional"))
    )
    (net (code "80") (name "Net-(U725-P2_7)") (class "Default")
      (node (ref "R2775") (pin "1") (pinfunction "1_1") (pintype "passive"))
      (node (ref "U725") (pin "24") (pinfunction "P2_7_24") (pintype "bidirectional"))
    )
    (net (code "81") (name "Net-(U725-SCL)") (class "Default")
      (node (ref "R2763") (pin "2") (pinfunction "2_2") (pintype "passive"))
      (node (ref "R2767") (pin "2") (pinfunction "2_2") (pintype "passive"))
      (node (ref "U725") (pin "29") (pinfunction "SCL_29") (pintype "input"))
    )
    (net (code "82") (name "Net-(U725-SDA)") (class "Default")
      (node (ref "R2761") (pin "2") (pinfunction "2_2") (pintype "passive"))
      (node (ref "R2769") (pin "2") (pinfunction "2_2") (pintype "passive"))
      (node (ref "U725") (pin "30") (pinfunction "SDA_30") (pintype "bidirectional"))
    )
    (net (code "83") (name "Net-(U725-~{INT})") (class "Default")
      (node (ref "R2746") (pin "2") (pinfunction "2_2") (pintype "passive"))
      (node (ref "R2754") (pin "2") (pinfunction "2_2") (pintype "passive"))
      (node (ref "R2756") (pin "2") (pinfunction "2_2") (pintype "passive"))
      (node (ref "U725") (pin "32") (pinfunction "~{INT}_32") (pintype "output"))
    )
    (net (code "84") (name "Net-(U725-~{RESET})") (class "Default")
      (node (ref "C926") (pin "1") (pinfunction "1_1") (pintype "passive"))
      (node (ref "R2747") (pin "2") (pinfunction "2_2") (pintype "passive"))
      (node (ref "R2753") (pin "2") (pinfunction "2_2") (pintype "passive"))
      (node (ref "U725") (pin "28") (pinfunction "~{RESET}_28") (pintype "input"))
    )
    (net (code "85") (name "PCIE_nWAKE") (class "Default")
      (node (ref "R2749") (pin "2") (pinfunction "2_2") (pintype "passive"))
    )
    (net (code "86") (name "PMIC_nINT") (class "Default")
      (node (ref "R2758") (pin "2") (pinfunction "2_2") (pintype "passive"))
      (node (ref "R2760") (pin "2") (pinfunction "2_2") (pintype "passive"))
    )
    (net (code "87") (name "RTC_nINTA") (class "Default")
      (node (ref "R2750") (pin "2") (pinfunction "2_2") (pintype "passive"))
    )
    (net (code "88") (name "SD3_nRST") (class "Default")
      (node (ref "R2764") (pin "2") (pinfunction "2_2") (pintype "passive"))
      (node (ref "R2768") (pin "1") (pinfunction "1_1") (pintype "passive"))
    )
    (net (code "89") (name "TCPC1_nINT") (class "Default")
      (node (ref "R2756") (pin "1") (pinfunction "1_1") (pintype "passive"))
    )
    (net (code "90") (name "TCPC_nINT") (class "Default")
      (node (ref "R2748") (pin "2") (pinfunction "2_2") (pintype "passive"))
    )
    (net (code "91") (name "U4_CSI_MCLK") (class "Default")
      (node (ref "R2740") (pin "1") (pinfunction "1_1") (pintype "passive"))
    )
    (net (code "92") (name "UART_nWAKE") (class "Default")
      (node (ref "R2751") (pin "2") (pinfunction "2_2") (pintype "passive"))
    )
    (net (code "93") (name "USB_I2C_SCL") (class "Default")
      (node (ref "R2742") (pin "1") (pinfunction "1_1") (pintype "passive"))
      (node (ref "R2743") (pin "1") (pinfunction "1_1") (pintype "passive"))
      (node (ref "TP1060") (pin "1") (pinfunction "TP_1") (pintype "passive"))
    )
    (net (code "94") (name "USB_I2C_SDA") (class "Default")
      (node (ref "R2741") (pin "1") (pinfunction "1_1") (pintype "passive"))
      (node (ref "R2744") (pin "1") (pinfunction "1_1") (pintype "passive"))
      (node (ref "TP1061") (pin "1") (pinfunction "TP_1") (pintype "passive"))
    )
    (net (code "95") (name "VDD_1V8") (class "Default")
      (node (ref "C1038") (pin "1") (pinfunction "1_1") (pintype "passive"))
      (node (ref "C920") (pin "1") (pinfunction "1_1") (pintype "passive"))
      (node (ref "R2745") (pin "2") (pinfunction "2_2") (pintype "passive"))
      (node (ref "U724") (pin "1") (pinfunction "VL_1") (pintype "power_in"))
      (node (ref "U743") (pin "5") (pinfunction "VCC_5") (pintype "power_in"))
    )
    (net (code "96") (name "VDD_3V3") (class "Default")
      (node (ref "C921") (pin "1") (pinfunction "1_1") (pintype "passive"))
      (node (ref "C925") (pin "1") (pinfunction "1_1") (pintype "passive"))
      (node (ref "R145") (pin "1") (pinfunction "1_1") (pintype "passive"))
      (node (ref "R2746") (pin "1") (pinfunction "1_1") (pintype "passive"))
      (node (ref "R2747") (pin "1") (pinfunction "1_1") (pintype "passive"))
      (node (ref "R2758") (pin "1") (pinfunction "1_1") (pintype "passive"))
      (node (ref "R3057") (pin "1") (pinfunction "1_1") (pintype "passive"))
      (node (ref "R3058") (pin "1") (pinfunction "1_1") (pintype "passive"))
      (node (ref "U724") (pin "6") (pinfunction "VCC_6") (pintype "power_in"))
      (node (ref "U725") (pin "27") (pinfunction "VDD_P_27") (pintype "power_in"))
      (node (ref "U725") (pin "31") (pinfunction "VDD_I2C_31") (pintype "power_in"))
    )
    (net (code "97") (name "VDD_5V") (class "Default")
      (node (ref "C917") (pin "1") (pinfunction "1_1") (pintype "passive"))
      (node (ref "R2734") (pin "2") (pinfunction "2_2") (pintype "passive"))
      (node (ref "U723") (pin "3") (pinfunction "VIN_3") (pintype "passive"))
    )
    (net (code "98") (name "Y3_EXP_nIRQ") (class "Default")
      (node (ref "R2754") (pin "1") (pinfunction "1_1") (pintype "passive"))
    )
    (net (code "99") (name "unconnected-(P6-Pad11)") (class "Default")
      (node (ref "P6") (pin "11") (pinfunction "11_11") (pintype "passive+no_connect"))
    )
    (net (code "100") (name "unconnected-(P6-Pad12)") (class "Default")
      (node (ref "P6") (pin "12") (pinfunction "12_12") (pintype "passive+no_connect"))
    )
    (net (code "101") (name "unconnected-(P6-Pad14)") (class "Default")
      (node (ref "P6") (pin "14") (pinfunction "14_14") (pintype "passive+no_connect"))
    )
    (net (code "102") (name "unconnected-(P6-Pad15)") (class "Default")
      (node (ref "P6") (pin "15") (pinfunction "15_15") (pintype "passive+no_connect"))
    )
    (net (code "103") (name "unconnected-(U743-NC-Pad1)") (class "Default")
      (node (ref "U743") (pin "1") (pinfunction "NC_1") (pintype "passive+no_connect"))
    )
  )
)
